# AFE_conn.net
KiCad netlist of a schematic drawn in Altium Designer
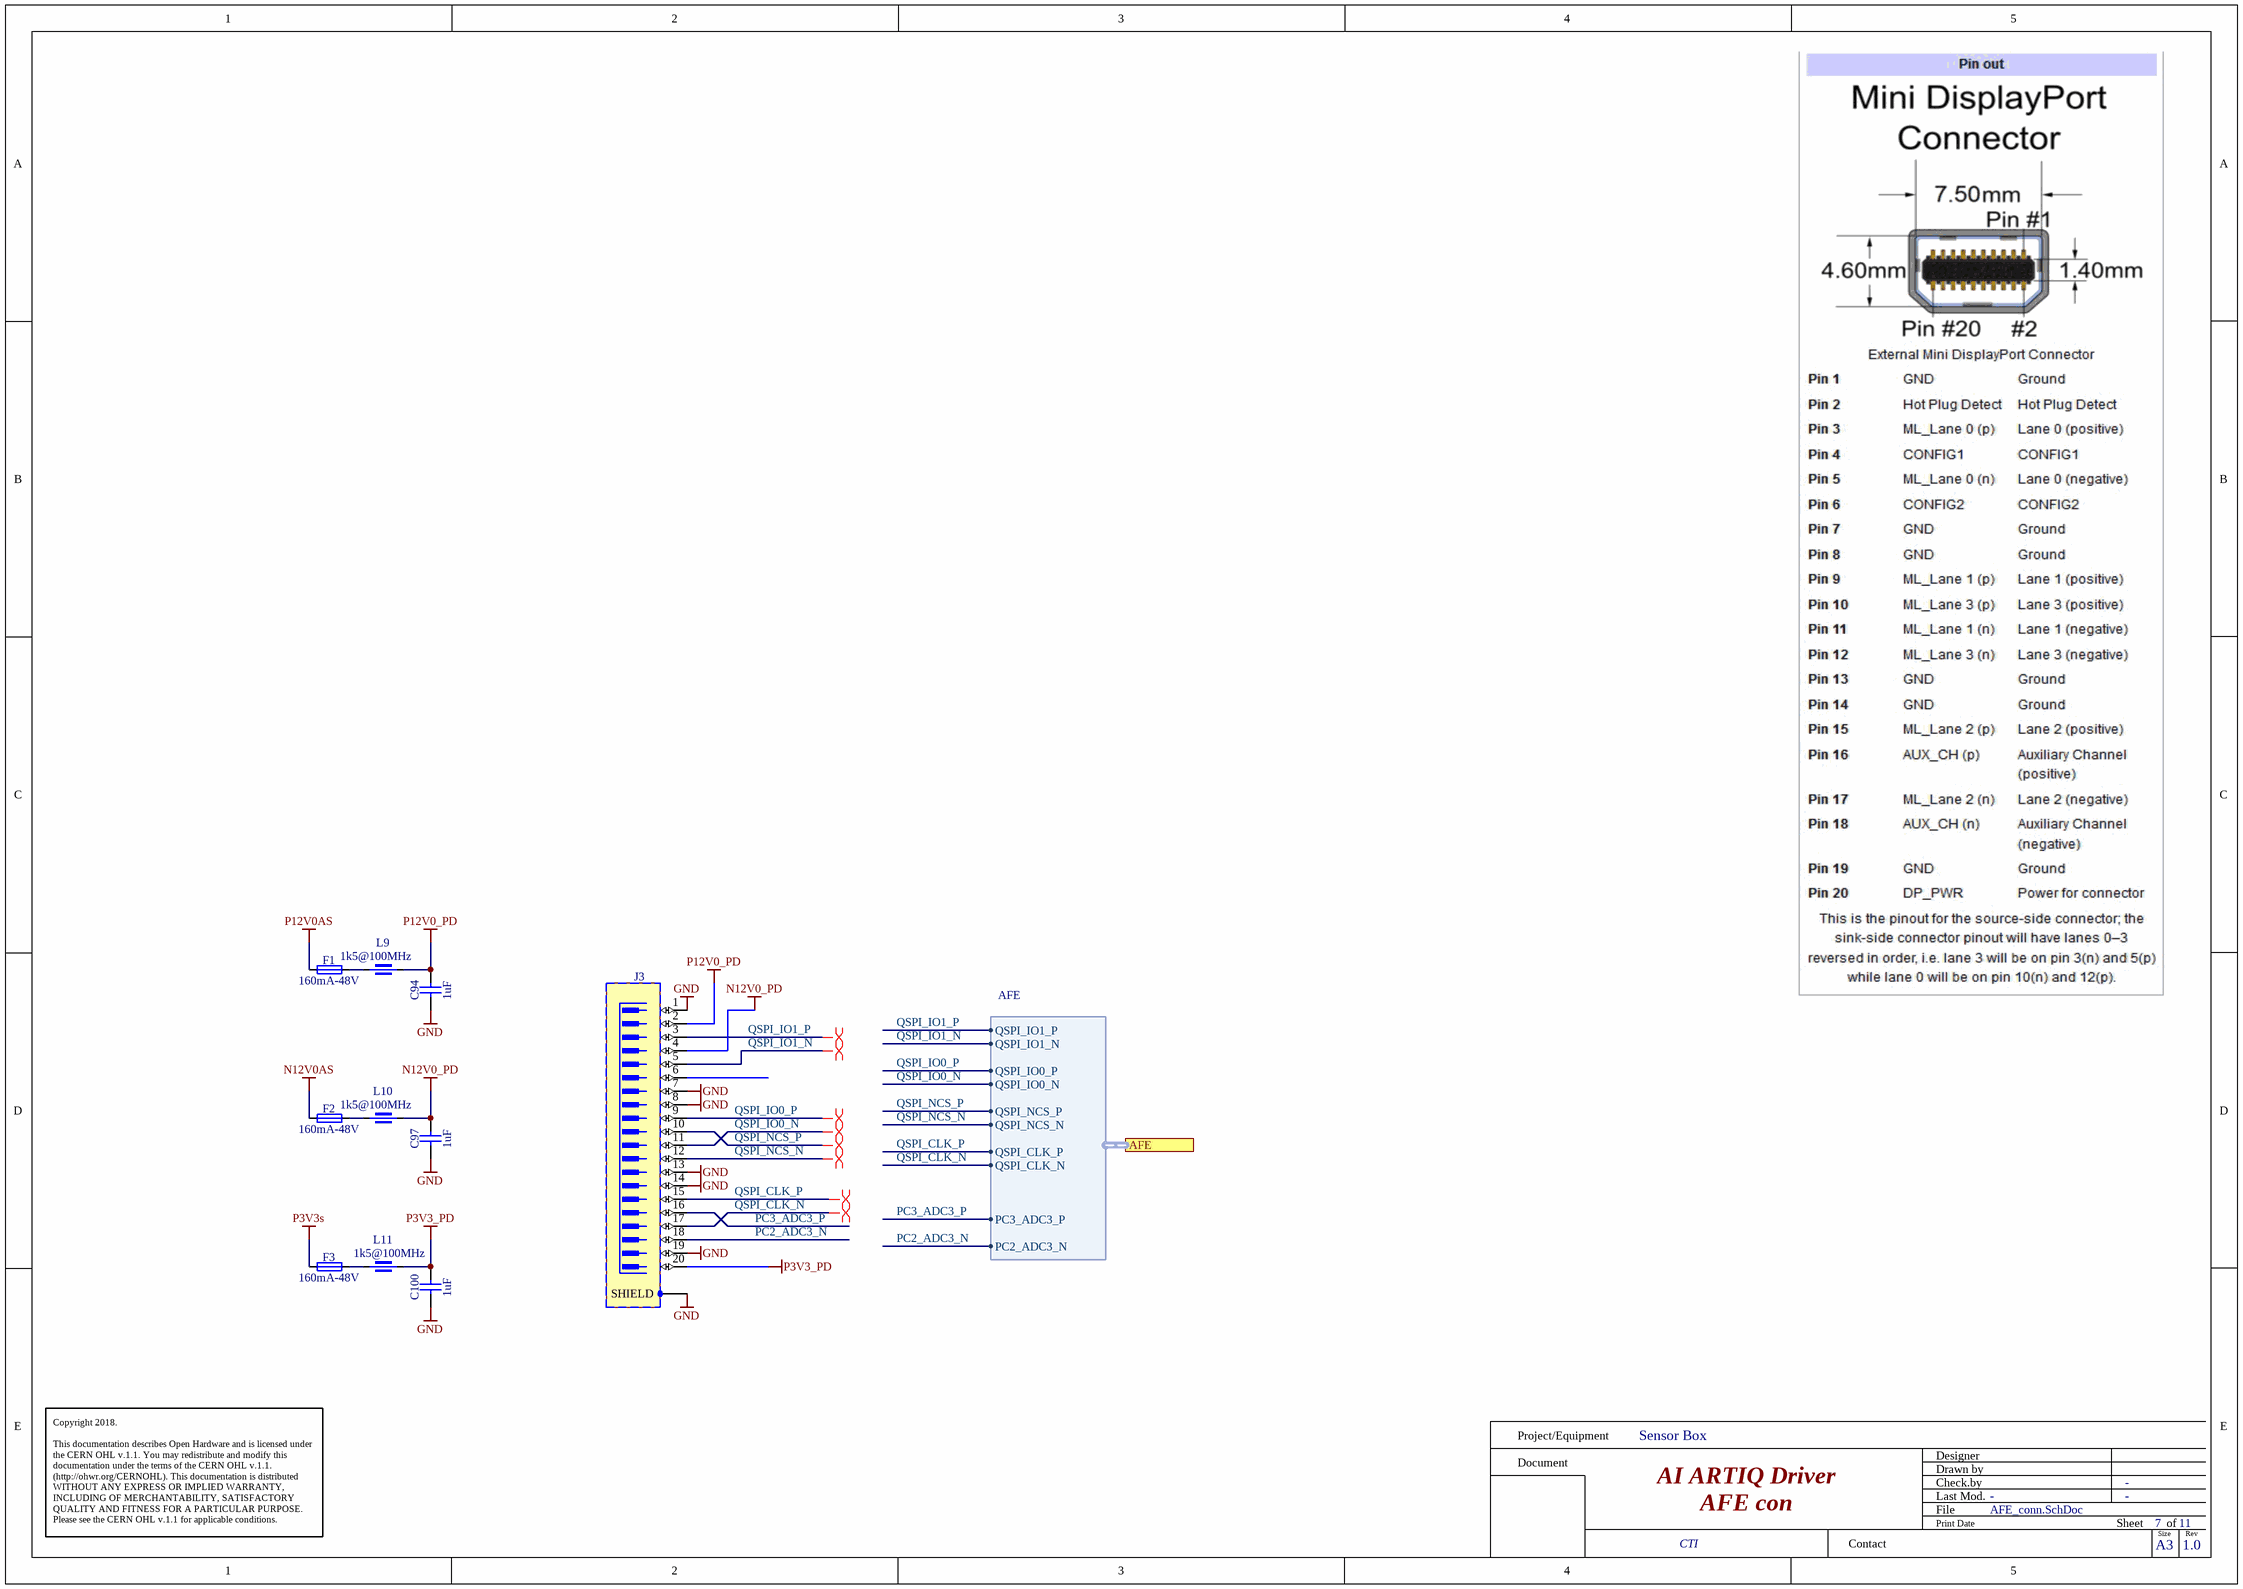
[diagram p0: AFE_conn.SchDoc]

(export (version "E")
  (design (tool "Eeschema 10.0.6"))
  (components
    (comp (ref "C94")
      (value "1uF")
      (footprint "CAPC2012X135N")
      (description "Non-polarised capacitor")
      (fields
        (field (name "PART NUMBER") "CC0805_1UF_16V_10%_X7R")
        (field (name "VOLTAGE") "16V")
        (field (name "AUTHOR") "CERN DEM JLC")
      )
      (libsource (lib "Capacitors") (part "Capacitor - non polarized"))
    )
    (comp (ref "C97")
      (value "1uF")
      (footprint "CAPC2012X135N")
      (description "Non-polarised capacitor")
      (fields
        (field (name "PART NUMBER") "CC0805_1UF_16V_10%_X7R")
        (field (name "VOLTAGE") "16V")
        (field (name "AUTHOR") "CERN DEM JLC")
      )
      (libsource (lib "Capacitors") (part "Capacitor - non polarized"))
    )
    (comp (ref "C100")
      (value "1uF")
      (footprint "CAPC2012X135N")
      (description "Non-polarised capacitor")
      (fields
        (field (name "PART NUMBER") "CC0805_1UF_16V_10%_X7R")
        (field (name "VOLTAGE") "16V")
        (field (name "AUTHOR") "CERN DEM JLC")
      )
      (libsource (lib "Capacitors") (part "Capacitor - non polarized"))
    )
    (comp (ref "F1")
      (value "160mA-48V")
      (footprint "FUSRC3216X100N")
      (description "Fuse")
      (fields
        (field (name "PART NUMBER") "FUSR1206_LITTELFUSE_NANOSMDC016F")
        (field (name "MANUFACTURER") "LITTELFUSE")
        (field (name "AUTHOR") "CERN DEM BC")
      )
      (libsource (lib "Eletro-mechanical") (part "Fuse"))
    )
    (comp (ref "F2")
      (value "160mA-48V")
      (footprint "FUSRC3216X100N")
      (description "Fuse")
      (fields
        (field (name "PART NUMBER") "FUSR1206_LITTELFUSE_NANOSMDC016F")
        (field (name "MANUFACTURER") "LITTELFUSE")
        (field (name "AUTHOR") "CERN DEM BC")
      )
      (libsource (lib "Eletro-mechanical") (part "Fuse"))
    )
    (comp (ref "F3")
      (value "160mA-48V")
      (footprint "FUSRC3216X100N")
      (description "Fuse")
      (fields
        (field (name "PART NUMBER") "FUSR1206_LITTELFUSE_NANOSMDC016F")
        (field (name "MANUFACTURER") "LITTELFUSE")
        (field (name "AUTHOR") "CERN DEM BC")
      )
      (libsource (lib "Eletro-mechanical") (part "Fuse"))
    )
    (comp (ref "J3")
      (value "Thunderbolt")
      (footprint "JAE_DP3AR020SU32JQ1R400")
      (description "Connector Mini DisplayPort 20 Male + 1 Shield")
      (fields
        (field (name "PART NUMBER") "JAE_DP3AR020SU32JQ1R400")
        (field (name "MANUFACTURER") "JAE (JAPAN AVIATION ELECTRONICS INDUSTRY)")
        (field (name "AUTHOR") "CERN DEM JLC")
      )
      (libsource (lib "Connectors") (part "Connector Mini DisplayPort 20 Male + 1 Shield"))
    )
    (comp (ref "L9")
      (value "1k5@100MHz")
      (footprint "INDC2012X110N")
      (fields
        (field (name "PART NUMBER") "IND0805_WURTH_742792097")
        (field (name "POWER") "1A")
        (field (name "TOLERANCE") "±25%")
        (field (name "AUTHOR") "CERN DEM MR")
      )
      (libsource (lib "Inductors & Transformers") (part "Ferrite Bead"))
    )
    (comp (ref "L10")
      (value "1k5@100MHz")
      (footprint "INDC2012X110N")
      (fields
        (field (name "PART NUMBER") "IND0805_WURTH_742792097")
        (field (name "POWER") "1A")
        (field (name "TOLERANCE") "±25%")
        (field (name "AUTHOR") "CERN DEM MR")
      )
      (libsource (lib "Inductors & Transformers") (part "Ferrite Bead"))
    )
    (comp (ref "L11")
      (value "1k5@100MHz")
      (footprint "INDC2012X110N")
      (fields
        (field (name "PART NUMBER") "IND0805_WURTH_742792097")
        (field (name "POWER") "1A")
        (field (name "TOLERANCE") "±25%")
        (field (name "AUTHOR") "CERN DEM MR")
      )
      (libsource (lib "Inductors & Transformers") (part "Ferrite Bead"))
    )
  )
  (nets
    (net (code "2") (name "/PC2_ADC3_N") (class "Default")
      (node (ref "J3") (pin "18") (pinfunction "18_18") (pintype "bidirectional"))
    )
    (net (code "3") (name "/PC3_ADC3_P") (class "Default")
      (node (ref "J3") (pin "16") (pinfunction "16_16") (pintype "bidirectional"))
    )
    (net (code "4") (name "/QSPI_CLK_N") (class "Default")
      (node (ref "J3") (pin "17") (pinfunction "17_17") (pintype "bidirectional"))
    )
    (net (code "5") (name "/QSPI_CLK_P") (class "Default")
      (node (ref "J3") (pin "15") (pinfunction "15_15") (pintype "bidirectional"))
    )
    (net (code "6") (name "/QSPI_IO0_N") (class "Default")
      (node (ref "J3") (pin "11") (pinfunction "11_11") (pintype "bidirectional"))
    )
    (net (code "7") (name "/QSPI_IO0_P") (class "Default")
      (node (ref "J3") (pin "9") (pinfunction "9_9") (pintype "bidirectional"))
    )
    (net (code "8") (name "/QSPI_IO1_N") (class "Default")
      (node (ref "J3") (pin "5") (pinfunction "5_5") (pintype "bidirectional"))
    )
    (net (code "9") (name "/QSPI_IO1_P") (class "Default")
      (node (ref "J3") (pin "3") (pinfunction "3_3") (pintype "bidirectional"))
    )
    (net (code "10") (name "/QSPI_NCS_N") (class "Default")
      (node (ref "J3") (pin "12") (pinfunction "12_12") (pintype "bidirectional"))
    )
    (net (code "11") (name "/QSPI_NCS_P") (class "Default")
      (node (ref "J3") (pin "10") (pinfunction "10_10") (pintype "bidirectional"))
    )
    (net (code "13") (name "GND") (class "Default")
      (node (ref "C100") (pin "1") (pinfunction "1_1") (pintype "passive"))
      (node (ref "C94") (pin "1") (pinfunction "1_1") (pintype "passive"))
      (node (ref "C97") (pin "1") (pinfunction "1_1") (pintype "passive"))
      (node (ref "J3") (pin "1") (pinfunction "1_1") (pintype "bidirectional"))
      (node (ref "J3") (pin "13") (pinfunction "13_13") (pintype "bidirectional"))
      (node (ref "J3") (pin "14") (pinfunction "14_14") (pintype "bidirectional"))
      (node (ref "J3") (pin "19") (pinfunction "19_19") (pintype "bidirectional"))
      (node (ref "J3") (pin "7") (pinfunction "7_7") (pintype "bidirectional"))
      (node (ref "J3") (pin "8") (pinfunction "8_8") (pintype "bidirectional"))
      (node (ref "J3") (pin "SHIELD") (pinfunction "SHIELD_SHIELD") (pintype "power_in"))
    )
    (net (code "14") (name "N12V0AS") (class "Default")
      (node (ref "F2") (pin "1") (pinfunction "1_1") (pintype "passive"))
    )
    (net (code "15") (name "N12V0_PD") (class "Default")
      (node (ref "C97") (pin "2") (pinfunction "2_2") (pintype "passive"))
      (node (ref "J3") (pin "4") (pinfunction "4_4") (pintype "bidirectional"))
      (node (ref "L10") (pin "2") (pinfunction "2_2") (pintype "passive"))
    )
    (net (code "16") (name "Net-(F1-Pad2)") (class "Default")
      (node (ref "F1") (pin "2") (pinfunction "2_2") (pintype "passive"))
      (node (ref "L9") (pin "1") (pinfunction "1_1") (pintype "passive"))
    )
    (net (code "17") (name "Net-(F2-Pad2)") (class "Default")
      (node (ref "F2") (pin "2") (pinfunction "2_2") (pintype "passive"))
      (node (ref "L10") (pin "1") (pinfunction "1_1") (pintype "passive"))
    )
    (net (code "18") (name "Net-(F3-Pad2)") (class "Default")
      (node (ref "F3") (pin "2") (pinfunction "2_2") (pintype "passive"))
      (node (ref "L11") (pin "1") (pinfunction "1_1") (pintype "passive"))
    )
    (net (code "19") (name "P3V3_PD") (class "Default")
      (node (ref "C100") (pin "2") (pinfunction "2_2") (pintype "passive"))
      (node (ref "J3") (pin "20") (pinfunction "20_20") (pintype "bidirectional"))
      (node (ref "L11") (pin "2") (pinfunction "2_2") (pintype "passive"))
    )
    (net (code "20") (name "P3V3s") (class "Default")
      (node (ref "F3") (pin "1") (pinfunction "1_1") (pintype "passive"))
    )
    (net (code "21") (name "P12V0AS") (class "Default")
      (node (ref "F1") (pin "1") (pinfunction "1_1") (pintype "passive"))
    )
    (net (code "22") (name "P12V0_PD") (class "Default")
      (node (ref "C94") (pin "2") (pinfunction "2_2") (pintype "passive"))
      (node (ref "J3") (pin "2") (pinfunction "2_2") (pintype "bidirectional"))
      (node (ref "L9") (pin "2") (pinfunction "2_2") (pintype "passive"))
    )
    (net (code "23") (name "unconnected-(J3-Pad6)") (class "Default")
      (node (ref "J3") (pin "6") (pinfunction "6_6") (pintype "bidirectional"))
    )
  )
)
